# PIN_1_0.net
KiCad netlist of a schematic drawn in EAGLE
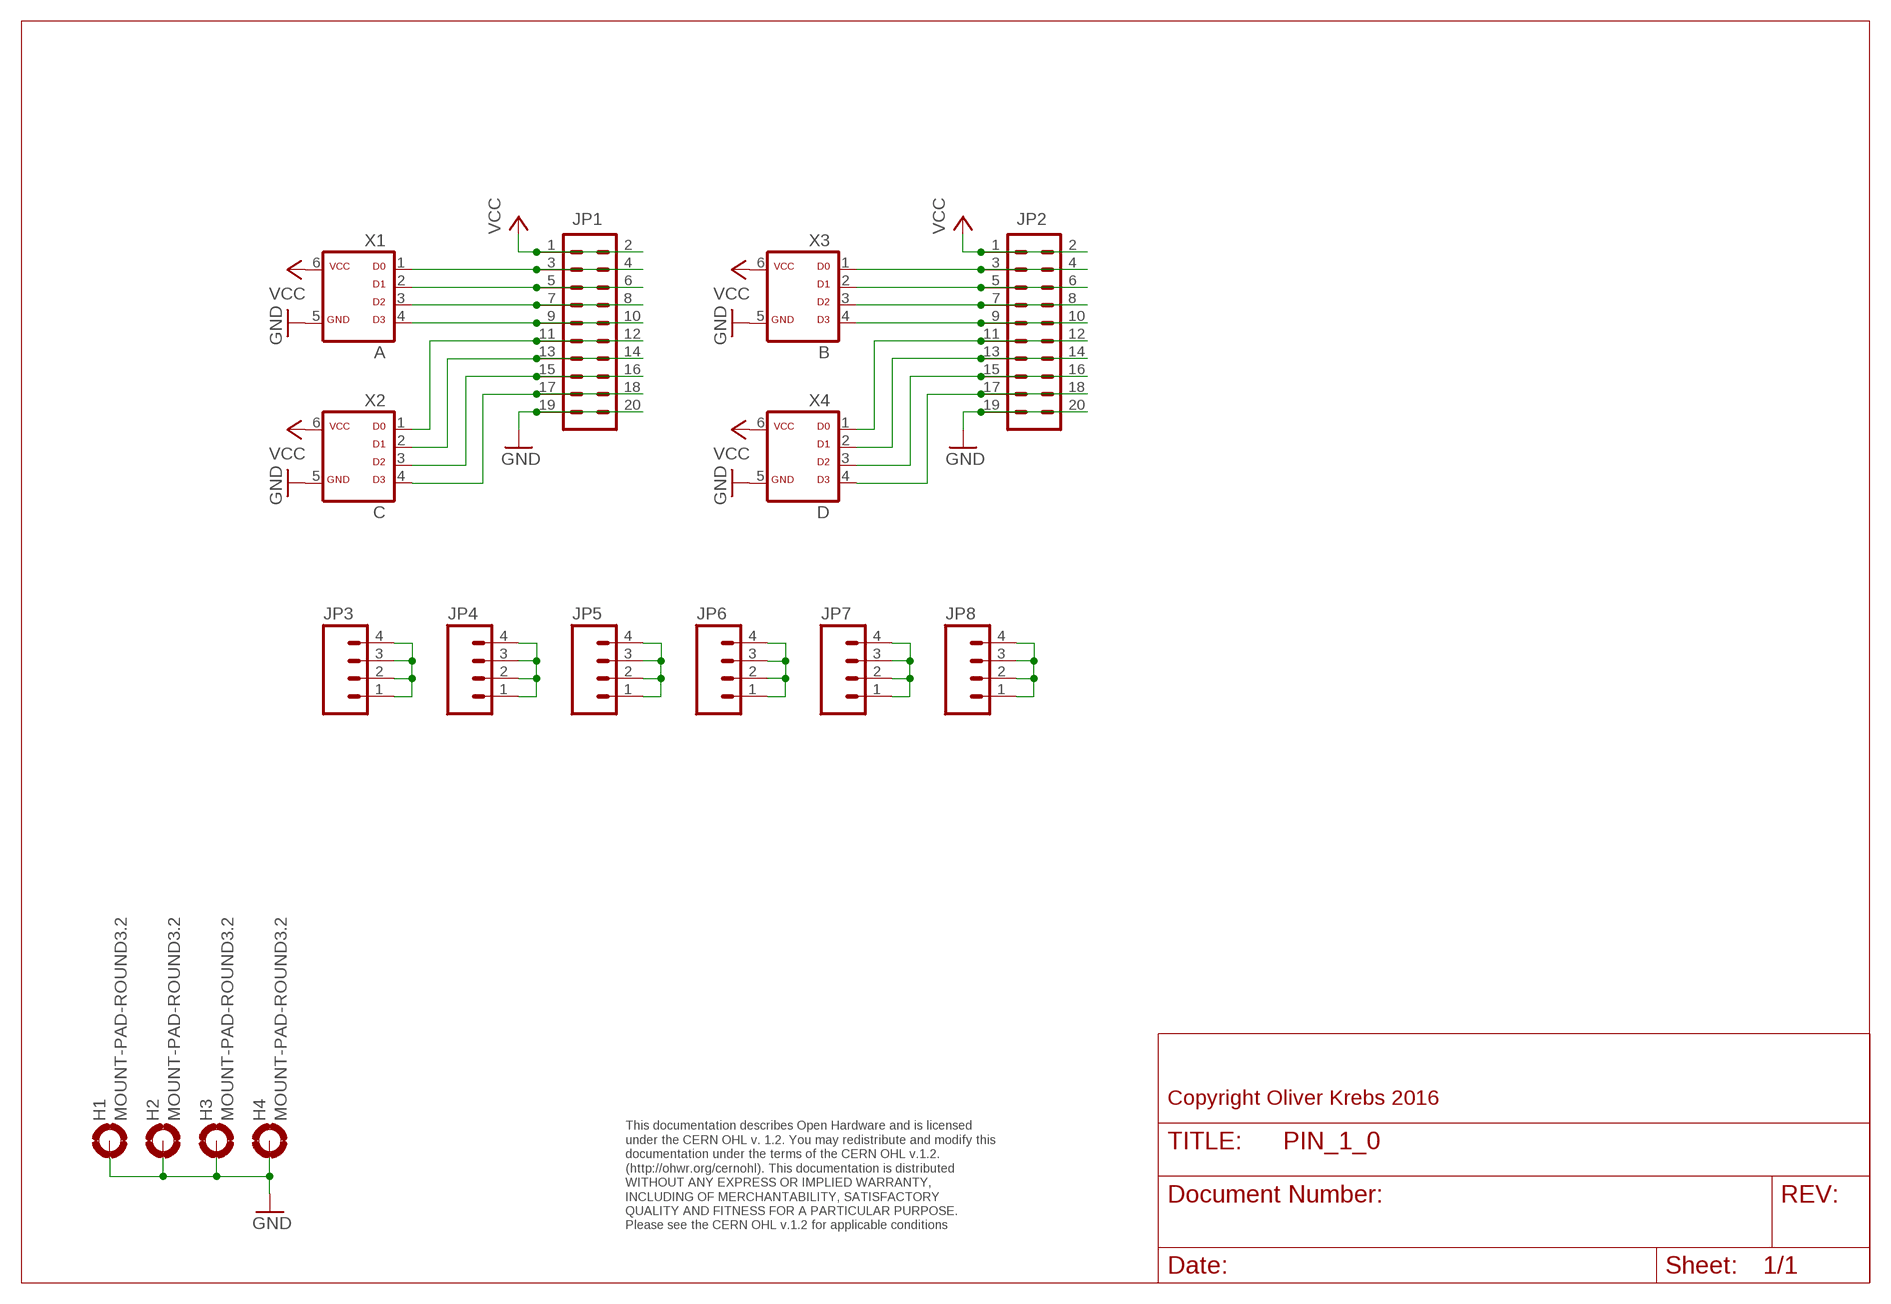
[diagram p0: schematic, sheet 1]

(export (version "E")
  (design (tool "Eeschema 10.0.6"))
  (components
    (comp (ref "H1")
      (value "MOUNT-PAD-ROUND3.2")
      (footprint "eagle-import:3,2-PAD")
      (libsource (lib "eagle-import") (part "MOUNT-PAD-ROUND3.2"))
    )
    (comp (ref "H2")
      (value "MOUNT-PAD-ROUND3.2")
      (footprint "eagle-import:3,2-PAD")
      (libsource (lib "eagle-import") (part "MOUNT-PAD-ROUND3.2"))
    )
    (comp (ref "H3")
      (value "MOUNT-PAD-ROUND3.2")
      (footprint "eagle-import:3,2-PAD")
      (libsource (lib "eagle-import") (part "MOUNT-PAD-ROUND3.2"))
    )
    (comp (ref "H4")
      (value "MOUNT-PAD-ROUND3.2")
      (footprint "eagle-import:3,2-PAD")
      (libsource (lib "eagle-import") (part "MOUNT-PAD-ROUND3.2"))
    )
    (comp (ref "JP1")
      (value "M10X2")
      (footprint "eagle-import:2X10")
      (libsource (lib "eagle-import") (part "M10X2"))
    )
    (comp (ref "JP2")
      (value "M10X2")
      (footprint "eagle-import:2X10")
      (libsource (lib "eagle-import") (part "M10X2"))
    )
    (comp (ref "JP3")
      (value "M04PTH")
      (footprint "eagle-import:1X04")
      (libsource (lib "eagle-import") (part "M04PTH"))
    )
    (comp (ref "JP4")
      (value "M04PTH")
      (footprint "eagle-import:1X04")
      (libsource (lib "eagle-import") (part "M04PTH"))
    )
    (comp (ref "JP5")
      (value "M04PTH")
      (footprint "eagle-import:1X04")
      (libsource (lib "eagle-import") (part "M04PTH"))
    )
    (comp (ref "JP6")
      (value "M04PTH")
      (footprint "eagle-import:1X04")
      (libsource (lib "eagle-import") (part "M04PTH"))
    )
    (comp (ref "JP7")
      (value "M04PTH")
      (footprint "eagle-import:1X04")
      (libsource (lib "eagle-import") (part "M04PTH"))
    )
    (comp (ref "JP8")
      (value "M04PTH")
      (footprint "eagle-import:1X04")
      (libsource (lib "eagle-import") (part "M04PTH"))
    )
    (comp (ref "X1")
      (value "A")
      (footprint "eagle-import:ML-6")
      (libsource (lib "eagle-import") (part "ML6D"))
    )
    (comp (ref "X2")
      (value "C")
      (footprint "eagle-import:ML-6")
      (libsource (lib "eagle-import") (part "ML6D"))
    )
    (comp (ref "X3")
      (value "B")
      (footprint "eagle-import:ML-6")
      (libsource (lib "eagle-import") (part "ML6D"))
    )
    (comp (ref "X4")
      (value "D")
      (footprint "eagle-import:ML-6")
      (libsource (lib "eagle-import") (part "ML6D"))
    )
  )
  (nets
    (net (code "1") (name "GND") (class "Default")
      (node (ref "H1") (pin "B3,2") (pinfunction "MOUNT_B3,2") (pintype "passive"))
      (node (ref "H2") (pin "B3,2") (pinfunction "MOUNT_B3,2") (pintype "passive"))
      (node (ref "H3") (pin "B3,2") (pinfunction "MOUNT_B3,2") (pintype "passive"))
      (node (ref "H4") (pin "B3,2") (pinfunction "MOUNT_B3,2") (pintype "passive"))
      (node (ref "JP1") (pin "19") (pinfunction "19_19") (pintype "passive"))
      (node (ref "JP1") (pin "20") (pinfunction "20_20") (pintype "passive"))
      (node (ref "JP2") (pin "19") (pinfunction "19_19") (pintype "passive"))
      (node (ref "JP2") (pin "20") (pinfunction "20_20") (pintype "passive"))
      (node (ref "X1") (pin "5") (pinfunction "5_5") (pintype "passive"))
      (node (ref "X2") (pin "5") (pinfunction "5_5") (pintype "passive"))
      (node (ref "X3") (pin "5") (pinfunction "5_5") (pintype "passive"))
      (node (ref "X4") (pin "5") (pinfunction "5_5") (pintype "passive"))
    )
    (net (code "2") (name "Net-(JP1-Pad3)") (class "Default")
      (node (ref "JP1") (pin "3") (pinfunction "3_3") (pintype "passive"))
      (node (ref "JP1") (pin "4") (pinfunction "4_4") (pintype "passive"))
      (node (ref "X1") (pin "1") (pinfunction "1_1") (pintype "passive"))
    )
    (net (code "3") (name "Net-(JP1-Pad5)") (class "Default")
      (node (ref "JP1") (pin "5") (pinfunction "5_5") (pintype "passive"))
      (node (ref "JP1") (pin "6") (pinfunction "6_6") (pintype "passive"))
      (node (ref "X1") (pin "2") (pinfunction "2_2") (pintype "passive"))
    )
    (net (code "4") (name "Net-(JP1-Pad7)") (class "Default")
      (node (ref "JP1") (pin "7") (pinfunction "7_7") (pintype "passive"))
      (node (ref "JP1") (pin "8") (pinfunction "8_8") (pintype "passive"))
      (node (ref "X1") (pin "3") (pinfunction "3_3") (pintype "passive"))
    )
    (net (code "5") (name "Net-(JP1-Pad10)") (class "Default")
      (node (ref "JP1") (pin "10") (pinfunction "10_10") (pintype "passive"))
      (node (ref "JP1") (pin "9") (pinfunction "9_9") (pintype "passive"))
      (node (ref "X1") (pin "4") (pinfunction "4_4") (pintype "passive"))
    )
    (net (code "6") (name "Net-(JP1-Pad11)") (class "Default")
      (node (ref "JP1") (pin "11") (pinfunction "11_11") (pintype "passive"))
      (node (ref "JP1") (pin "12") (pinfunction "12_12") (pintype "passive"))
      (node (ref "X2") (pin "1") (pinfunction "1_1") (pintype "passive"))
    )
    (net (code "7") (name "Net-(JP1-Pad13)") (class "Default")
      (node (ref "JP1") (pin "13") (pinfunction "13_13") (pintype "passive"))
      (node (ref "JP1") (pin "14") (pinfunction "14_14") (pintype "passive"))
      (node (ref "X2") (pin "2") (pinfunction "2_2") (pintype "passive"))
    )
    (net (code "8") (name "Net-(JP1-Pad15)") (class "Default")
      (node (ref "JP1") (pin "15") (pinfunction "15_15") (pintype "passive"))
      (node (ref "JP1") (pin "16") (pinfunction "16_16") (pintype "passive"))
      (node (ref "X2") (pin "3") (pinfunction "3_3") (pintype "passive"))
    )
    (net (code "9") (name "Net-(JP1-Pad17)") (class "Default")
      (node (ref "JP1") (pin "17") (pinfunction "17_17") (pintype "passive"))
      (node (ref "JP1") (pin "18") (pinfunction "18_18") (pintype "passive"))
      (node (ref "X2") (pin "4") (pinfunction "4_4") (pintype "passive"))
    )
    (net (code "10") (name "Net-(JP2-Pad3)") (class "Default")
      (node (ref "JP2") (pin "3") (pinfunction "3_3") (pintype "passive"))
      (node (ref "JP2") (pin "4") (pinfunction "4_4") (pintype "passive"))
      (node (ref "X3") (pin "1") (pinfunction "1_1") (pintype "passive"))
    )
    (net (code "11") (name "Net-(JP2-Pad5)") (class "Default")
      (node (ref "JP2") (pin "5") (pinfunction "5_5") (pintype "passive"))
      (node (ref "JP2") (pin "6") (pinfunction "6_6") (pintype "passive"))
      (node (ref "X3") (pin "2") (pinfunction "2_2") (pintype "passive"))
    )
    (net (code "12") (name "Net-(JP2-Pad7)") (class "Default")
      (node (ref "JP2") (pin "7") (pinfunction "7_7") (pintype "passive"))
      (node (ref "JP2") (pin "8") (pinfunction "8_8") (pintype "passive"))
      (node (ref "X3") (pin "3") (pinfunction "3_3") (pintype "passive"))
    )
    (net (code "13") (name "Net-(JP2-Pad10)") (class "Default")
      (node (ref "JP2") (pin "10") (pinfunction "10_10") (pintype "passive"))
      (node (ref "JP2") (pin "9") (pinfunction "9_9") (pintype "passive"))
      (node (ref "X3") (pin "4") (pinfunction "4_4") (pintype "passive"))
    )
    (net (code "14") (name "Net-(JP2-Pad11)") (class "Default")
      (node (ref "JP2") (pin "11") (pinfunction "11_11") (pintype "passive"))
      (node (ref "JP2") (pin "12") (pinfunction "12_12") (pintype "passive"))
      (node (ref "X4") (pin "1") (pinfunction "1_1") (pintype "passive"))
    )
    (net (code "15") (name "Net-(JP2-Pad13)") (class "Default")
      (node (ref "JP2") (pin "13") (pinfunction "13_13") (pintype "passive"))
      (node (ref "JP2") (pin "14") (pinfunction "14_14") (pintype "passive"))
      (node (ref "X4") (pin "2") (pinfunction "2_2") (pintype "passive"))
    )
    (net (code "16") (name "Net-(JP2-Pad15)") (class "Default")
      (node (ref "JP2") (pin "15") (pinfunction "15_15") (pintype "passive"))
      (node (ref "JP2") (pin "16") (pinfunction "16_16") (pintype "passive"))
      (node (ref "X4") (pin "3") (pinfunction "3_3") (pintype "passive"))
    )
    (net (code "17") (name "Net-(JP2-Pad17)") (class "Default")
      (node (ref "JP2") (pin "17") (pinfunction "17_17") (pintype "passive"))
      (node (ref "JP2") (pin "18") (pinfunction "18_18") (pintype "passive"))
      (node (ref "X4") (pin "4") (pinfunction "4_4") (pintype "passive"))
    )
    (net (code "18") (name "Net-(JP3-Pad1)") (class "Default")
      (node (ref "JP3") (pin "1") (pinfunction "1_1") (pintype "passive"))
      (node (ref "JP3") (pin "2") (pinfunction "2_2") (pintype "passive"))
      (node (ref "JP3") (pin "3") (pinfunction "3_3") (pintype "passive"))
      (node (ref "JP3") (pin "4") (pinfunction "4_4") (pintype "passive"))
    )
    (net (code "19") (name "Net-(JP4-Pad1)") (class "Default")
      (node (ref "JP4") (pin "1") (pinfunction "1_1") (pintype "passive"))
      (node (ref "JP4") (pin "2") (pinfunction "2_2") (pintype "passive"))
      (node (ref "JP4") (pin "3") (pinfunction "3_3") (pintype "passive"))
      (node (ref "JP4") (pin "4") (pinfunction "4_4") (pintype "passive"))
    )
    (net (code "20") (name "Net-(JP5-Pad1)") (class "Default")
      (node (ref "JP5") (pin "1") (pinfunction "1_1") (pintype "passive"))
      (node (ref "JP5") (pin "2") (pinfunction "2_2") (pintype "passive"))
      (node (ref "JP5") (pin "3") (pinfunction "3_3") (pintype "passive"))
      (node (ref "JP5") (pin "4") (pinfunction "4_4") (pintype "passive"))
    )
    (net (code "21") (name "Net-(JP6-Pad1)") (class "Default")
      (node (ref "JP6") (pin "1") (pinfunction "1_1") (pintype "passive"))
      (node (ref "JP6") (pin "2") (pinfunction "2_2") (pintype "passive"))
      (node (ref "JP6") (pin "3") (pinfunction "3_3") (pintype "passive"))
      (node (ref "JP6") (pin "4") (pinfunction "4_4") (pintype "passive"))
    )
    (net (code "22") (name "Net-(JP7-Pad1)") (class "Default")
      (node (ref "JP7") (pin "1") (pinfunction "1_1") (pintype "passive"))
      (node (ref "JP7") (pin "2") (pinfunction "2_2") (pintype "passive"))
      (node (ref "JP7") (pin "3") (pinfunction "3_3") (pintype "passive"))
      (node (ref "JP7") (pin "4") (pinfunction "4_4") (pintype "passive"))
    )
    (net (code "23") (name "Net-(JP8-Pad1)") (class "Default")
      (node (ref "JP8") (pin "1") (pinfunction "1_1") (pintype "passive"))
      (node (ref "JP8") (pin "2") (pinfunction "2_2") (pintype "passive"))
      (node (ref "JP8") (pin "3") (pinfunction "3_3") (pintype "passive"))
      (node (ref "JP8") (pin "4") (pinfunction "4_4") (pintype "passive"))
    )
    (net (code "24") (name "VCC") (class "Default")
      (node (ref "JP1") (pin "1") (pinfunction "1_1") (pintype "passive"))
      (node (ref "JP1") (pin "2") (pinfunction "2_2") (pintype "passive"))
      (node (ref "JP2") (pin "1") (pinfunction "1_1") (pintype "passive"))
      (node (ref "JP2") (pin "2") (pinfunction "2_2") (pintype "passive"))
      (node (ref "X1") (pin "6") (pinfunction "6_6") (pintype "passive"))
      (node (ref "X2") (pin "6") (pinfunction "6_6") (pintype "passive"))
      (node (ref "X3") (pin "6") (pinfunction "6_6") (pintype "passive"))
      (node (ref "X4") (pin "6") (pinfunction "6_6") (pintype "passive"))
    )
  )
)
